# explorator_breakout_pcb_40mm.net
KiCad netlist of a schematic drawn in EAGLE
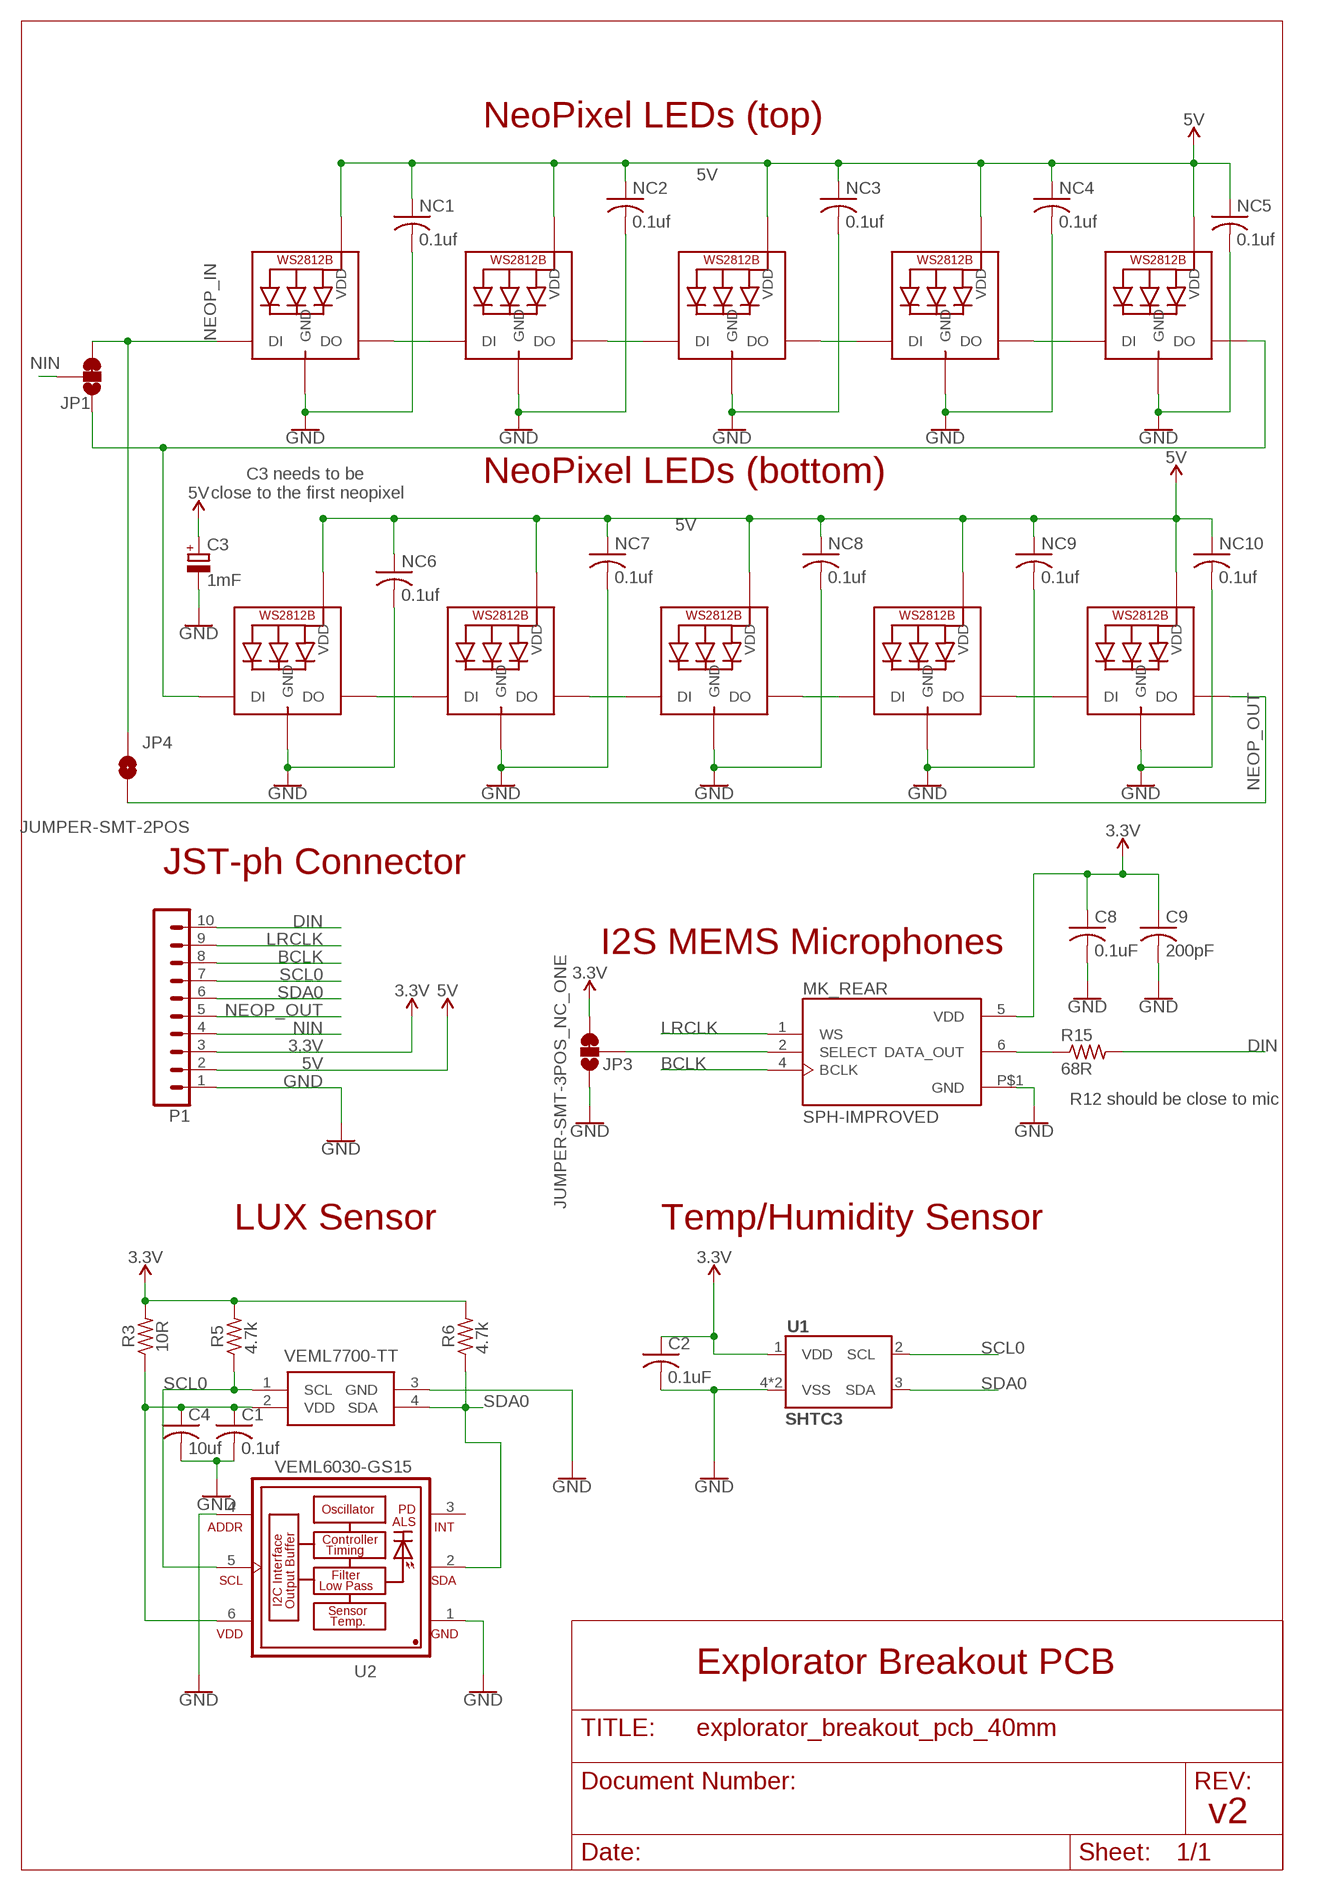
[diagram p0: schematic, sheet 1]

(export (version "E")
  (design (tool "Eeschema 10.0.6"))
  (components
    (comp (ref "C1")
      (value "0.1uf")
      (footprint "eagle-import:C0805")
      (libsource (lib "eagle-import") (part "C-USC0805"))
    )
    (comp (ref "C2")
      (value "0.1uF")
      (footprint "eagle-import:C0805")
      (libsource (lib "eagle-import") (part "C-USC0805"))
    )
    (comp (ref "C3")
      (value "1mF")
      (footprint "eagle-import:153CLV-1012")
      (libsource (lib "eagle-import") (part "CPOL-EU153CLV-1012"))
    )
    (comp (ref "C4")
      (value "10uf")
      (footprint "eagle-import:C0805")
      (libsource (lib "eagle-import") (part "C-USC0805"))
    )
    (comp (ref "C8")
      (value "0.1uF")
      (footprint "eagle-import:C0805")
      (libsource (lib "eagle-import") (part "C-USC0805"))
    )
    (comp (ref "C9")
      (value "200pF")
      (footprint "eagle-import:C0805")
      (libsource (lib "eagle-import") (part "C-USC0805"))
    )
    (comp (ref "JP1")
      (value "JUMPER-SMT-3POS_NC_ONE")
      (footprint "eagle-import:SMT-JUMPER_3_1-NC_TRACE_NO-SILK")
      (libsource (lib "eagle-import") (part "JUMPER-SMT-3POS_NC_ONE"))
    )
    (comp (ref "JP3")
      (value "JUMPER-SMT-3POS_NC_ONE")
      (footprint "eagle-import:SMT-JUMPER_3_1-NC_TRACE_NO-SILK")
      (libsource (lib "eagle-import") (part "JUMPER-SMT-3POS_NC_ONE"))
    )
    (comp (ref "JP4")
      (value "JUMPER-SMT-2POS")
      (footprint "eagle-import:SMT-JUMPER_2_NO_NO-SILK")
      (libsource (lib "eagle-import") (part "JUMPER-SMT-2POS"))
    )
    (comp (ref "MK_REAR")
      (value "SPH-IMPROVED")
      (footprint "eagle-import:MIC_SPH0645LM4H-B_LARGER_RING")
      (libsource (lib "eagle-import") (part "SPH-IMPROVED"))
    )
    (comp (ref "NC1")
      (value "0.1uf")
      (footprint "eagle-import:C0805")
      (libsource (lib "eagle-import") (part "C-USC0805"))
    )
    (comp (ref "NC2")
      (value "0.1uf")
      (footprint "eagle-import:C0805")
      (libsource (lib "eagle-import") (part "C-USC0805"))
    )
    (comp (ref "NC3")
      (value "0.1uf")
      (footprint "eagle-import:C0805")
      (libsource (lib "eagle-import") (part "C-USC0805"))
    )
    (comp (ref "NC4")
      (value "0.1uf")
      (footprint "eagle-import:C0805")
      (libsource (lib "eagle-import") (part "C-USC0805"))
    )
    (comp (ref "NC5")
      (value "0.1uf")
      (footprint "eagle-import:C0805")
      (libsource (lib "eagle-import") (part "C-USC0805"))
    )
    (comp (ref "NC6")
      (value "0.1uf")
      (footprint "eagle-import:C0805")
      (libsource (lib "eagle-import") (part "C-USC0805"))
    )
    (comp (ref "NC7")
      (value "0.1uf")
      (footprint "eagle-import:C0805")
      (libsource (lib "eagle-import") (part "C-USC0805"))
    )
    (comp (ref "NC8")
      (value "0.1uf")
      (footprint "eagle-import:C0805")
      (libsource (lib "eagle-import") (part "C-USC0805"))
    )
    (comp (ref "NC9")
      (value "0.1uf")
      (footprint "eagle-import:C0805")
      (libsource (lib "eagle-import") (part "C-USC0805"))
    )
    (comp (ref "NC10")
      (value "0.1uf")
      (footprint "eagle-import:C0805")
      (libsource (lib "eagle-import") (part "C-USC0805"))
    )
    (comp (ref "NEO_01")
      (value "WS2812")
      (footprint "eagle-import:WS2812B")
      (libsource (lib "eagle-import") (part "WS2812"))
    )
    (comp (ref "NEO_02")
      (value "WS2812")
      (footprint "eagle-import:WS2812B")
      (libsource (lib "eagle-import") (part "WS2812"))
    )
    (comp (ref "NEO_03")
      (value "WS2812")
      (footprint "eagle-import:WS2812B")
      (libsource (lib "eagle-import") (part "WS2812"))
    )
    (comp (ref "NEO_04")
      (value "WS2812")
      (footprint "eagle-import:WS2812B")
      (libsource (lib "eagle-import") (part "WS2812"))
    )
    (comp (ref "NEO_05")
      (value "WS2812")
      (footprint "eagle-import:WS2812B")
      (libsource (lib "eagle-import") (part "WS2812"))
    )
    (comp (ref "NEO_06")
      (value "WS2812")
      (footprint "eagle-import:WS2812B")
      (libsource (lib "eagle-import") (part "WS2812"))
    )
    (comp (ref "NEO_07")
      (value "WS2812")
      (footprint "eagle-import:WS2812B")
      (libsource (lib "eagle-import") (part "WS2812"))
    )
    (comp (ref "NEO_08")
      (value "WS2812")
      (footprint "eagle-import:WS2812B")
      (libsource (lib "eagle-import") (part "WS2812"))
    )
    (comp (ref "NEO_09")
      (value "WS2812")
      (footprint "eagle-import:WS2812B")
      (libsource (lib "eagle-import") (part "WS2812"))
    )
    (comp (ref "NEO_10")
      (value "WS2812")
      (footprint "eagle-import:WS2812B")
      (libsource (lib "eagle-import") (part "WS2812"))
    )
    (comp (ref "P1")
      (value "B10B-PH-K")
      (footprint "eagle-import:B10B-PH-K")
      (libsource (lib "eagle-import") (part "B10B-PH-K"))
    )
    (comp (ref "R3")
      (value "10R")
      (footprint "eagle-import:R0805")
      (libsource (lib "eagle-import") (part "R-US_R0805"))
    )
    (comp (ref "R5")
      (value "4.7k")
      (footprint "eagle-import:R0805")
      (libsource (lib "eagle-import") (part "R-US_R0805"))
    )
    (comp (ref "R6")
      (value "4.7k")
      (footprint "eagle-import:R0805")
      (libsource (lib "eagle-import") (part "R-US_R0805"))
    )
    (comp (ref "R15")
      (value "68R")
      (footprint "eagle-import:R0805")
      (libsource (lib "eagle-import") (part "R-US_R0805"))
    )
    (comp (ref "U1")
      (value "SHTC3")
      (footprint "eagle-import:SHTC3")
      (libsource (lib "eagle-import") (part "SHTC3"))
    )
    (comp (ref "U2")
      (value "VEML6030-GS15")
      (footprint "eagle-import:VISHAY_VEML6030_2X2X0.87")
      (fields (field (name "MF") "Vishay Semiconductor"))
      (libsource (lib "eagle-import") (part "VEML6030-GS15"))
    )
    (comp (ref "VEML_F")
      (value "VEML7700-TT")
      (footprint "eagle-import:VEML7700")
      (fields (field (name "MOUSER_PART_NUMBER") "78-VEML7700-TT") (field (name "RS_PART_NUMBER") "1226791P"))
      (libsource (lib "eagle-import") (part "VEML7700-TT"))
    )
  )
  (nets
    (net (code "1") (name "/BCLK") (class "Default")
      (node (ref "MK_REAR") (pin "4") (pinfunction "BCLK_4") (pintype "input"))
      (node (ref "P1") (pin "8") (pinfunction "8_8") (pintype "passive"))
    )
    (net (code "2") (name "/DIN") (class "Default")
      (node (ref "P1") (pin "10") (pinfunction "10_10") (pintype "passive"))
      (node (ref "R15") (pin "2") (pinfunction "2_2") (pintype "passive"))
    )
    (net (code "3") (name "/LRCLK") (class "Default")
      (node (ref "MK_REAR") (pin "1") (pinfunction "WS_1") (pintype "input"))
      (node (ref "P1") (pin "9") (pinfunction "9_9") (pintype "passive"))
    )
    (net (code "4") (name "/NEOP_IN") (class "Default")
      (node (ref "JP1") (pin "3") (pinfunction "3_3") (pintype "passive"))
      (node (ref "JP4") (pin "2") (pinfunction "2_2") (pintype "passive"))
      (node (ref "NEO_01") (pin "4-DIN") (pinfunction "DI_4-DIN") (pintype "input"))
    )
    (net (code "5") (name "/NEOP_OUT") (class "Default")
      (node (ref "JP4") (pin "1") (pinfunction "1_1") (pintype "passive"))
      (node (ref "NEO_10") (pin "2-DOUT") (pinfunction "DO_2-DOUT") (pintype "output"))
      (node (ref "P1") (pin "5") (pinfunction "5_5") (pintype "passive"))
    )
    (net (code "6") (name "/NIN") (class "Default")
      (node (ref "JP1") (pin "2") (pinfunction "2_2") (pintype "passive"))
      (node (ref "P1") (pin "4") (pinfunction "4_4") (pintype "passive"))
    )
    (net (code "7") (name "/SCL0") (class "Default")
      (node (ref "P1") (pin "7") (pinfunction "7_7") (pintype "passive"))
      (node (ref "R5") (pin "1") (pinfunction "1_1") (pintype "passive"))
      (node (ref "U1") (pin "2") (pinfunction "SCL_2") (pintype "bidirectional"))
      (node (ref "U2") (pin "5") (pinfunction "SCL_5") (pintype "input"))
      (node (ref "VEML_F") (pin "1") (pinfunction "SCL_1") (pintype "bidirectional"))
    )
    (net (code "8") (name "/SDA0") (class "Default")
      (node (ref "P1") (pin "6") (pinfunction "6_6") (pintype "passive"))
      (node (ref "R6") (pin "1") (pinfunction "1_1") (pintype "passive"))
      (node (ref "U1") (pin "3") (pinfunction "SDA_3") (pintype "bidirectional"))
      (node (ref "U2") (pin "2") (pinfunction "SDA_2") (pintype "bidirectional"))
      (node (ref "VEML_F") (pin "4") (pinfunction "SDA_4") (pintype "bidirectional"))
    )
    (net (code "9") (name "3.3V") (class "Default")
      (node (ref "C2") (pin "1") (pinfunction "1_1") (pintype "passive"))
      (node (ref "C8") (pin "1") (pinfunction "1_1") (pintype "passive"))
      (node (ref "C9") (pin "1") (pinfunction "1_1") (pintype "passive"))
      (node (ref "JP3") (pin "3") (pinfunction "3_3") (pintype "passive"))
      (node (ref "MK_REAR") (pin "5") (pinfunction "VDD_5") (pintype "power_in"))
      (node (ref "P1") (pin "3") (pinfunction "3_3") (pintype "passive"))
      (node (ref "R3") (pin "2") (pinfunction "2_2") (pintype "passive"))
      (node (ref "R5") (pin "2") (pinfunction "2_2") (pintype "passive"))
      (node (ref "R6") (pin "2") (pinfunction "2_2") (pintype "passive"))
      (node (ref "U1") (pin "1") (pinfunction "VDD_1") (pintype "bidirectional"))
    )
    (net (code "10") (name "5V") (class "Default")
      (node (ref "C3") (pin "+") (pinfunction "+_+") (pintype "passive"))
      (node (ref "NC1") (pin "1") (pinfunction "1_1") (pintype "passive"))
      (node (ref "NC10") (pin "1") (pinfunction "1_1") (pintype "passive"))
      (node (ref "NC2") (pin "1") (pinfunction "1_1") (pintype "passive"))
      (node (ref "NC3") (pin "1") (pinfunction "1_1") (pintype "passive"))
      (node (ref "NC4") (pin "1") (pinfunction "1_1") (pintype "passive"))
      (node (ref "NC5") (pin "1") (pinfunction "1_1") (pintype "passive"))
      (node (ref "NC6") (pin "1") (pinfunction "1_1") (pintype "passive"))
      (node (ref "NC7") (pin "1") (pinfunction "1_1") (pintype "passive"))
      (node (ref "NC8") (pin "1") (pinfunction "1_1") (pintype "passive"))
      (node (ref "NC9") (pin "1") (pinfunction "1_1") (pintype "passive"))
      (node (ref "NEO_01") (pin "1-VDD") (pinfunction "VDD_1-VDD") (pintype "power_in"))
      (node (ref "NEO_02") (pin "1-VDD") (pinfunction "VDD_1-VDD") (pintype "power_in"))
      (node (ref "NEO_03") (pin "1-VDD") (pinfunction "VDD_1-VDD") (pintype "power_in"))
      (node (ref "NEO_04") (pin "1-VDD") (pinfunction "VDD_1-VDD") (pintype "power_in"))
      (node (ref "NEO_05") (pin "1-VDD") (pinfunction "VDD_1-VDD") (pintype "power_in"))
      (node (ref "NEO_06") (pin "1-VDD") (pinfunction "VDD_1-VDD") (pintype "power_in"))
      (node (ref "NEO_07") (pin "1-VDD") (pinfunction "VDD_1-VDD") (pintype "power_in"))
      (node (ref "NEO_08") (pin "1-VDD") (pinfunction "VDD_1-VDD") (pintype "power_in"))
      (node (ref "NEO_09") (pin "1-VDD") (pinfunction "VDD_1-VDD") (pintype "power_in"))
      (node (ref "NEO_10") (pin "1-VDD") (pinfunction "VDD_1-VDD") (pintype "power_in"))
      (node (ref "P1") (pin "2") (pinfunction "2_2") (pintype "passive"))
    )
    (net (code "11") (name "GND") (class "Default")
      (node (ref "C1") (pin "2") (pinfunction "2_2") (pintype "passive"))
      (node (ref "C2") (pin "2") (pinfunction "2_2") (pintype "passive"))
      (node (ref "C3") (pin "-") (pinfunction "-_-") (pintype "passive"))
      (node (ref "C4") (pin "2") (pinfunction "2_2") (pintype "passive"))
      (node (ref "C8") (pin "2") (pinfunction "2_2") (pintype "passive"))
      (node (ref "C9") (pin "2") (pinfunction "2_2") (pintype "passive"))
      (node (ref "JP3") (pin "1") (pinfunction "1_1") (pintype "passive"))
      (node (ref "MK_REAR") (pin "P$1") (pinfunction "GND_P$1") (pintype "power_in"))
      (node (ref "NC1") (pin "2") (pinfunction "2_2") (pintype "passive"))
      (node (ref "NC10") (pin "2") (pinfunction "2_2") (pintype "passive"))
      (node (ref "NC2") (pin "2") (pinfunction "2_2") (pintype "passive"))
      (node (ref "NC3") (pin "2") (pinfunction "2_2") (pintype "passive"))
      (node (ref "NC4") (pin "2") (pinfunction "2_2") (pintype "passive"))
      (node (ref "NC5") (pin "2") (pinfunction "2_2") (pintype "passive"))
      (node (ref "NC6") (pin "2") (pinfunction "2_2") (pintype "passive"))
      (node (ref "NC7") (pin "2") (pinfunction "2_2") (pintype "passive"))
      (node (ref "NC8") (pin "2") (pinfunction "2_2") (pintype "passive"))
      (node (ref "NC9") (pin "2") (pinfunction "2_2") (pintype "passive"))
      (node (ref "NEO_01") (pin "3-GND") (pinfunction "GND_3-GND") (pintype "power_in"))
      (node (ref "NEO_02") (pin "3-GND") (pinfunction "GND_3-GND") (pintype "power_in"))
      (node (ref "NEO_03") (pin "3-GND") (pinfunction "GND_3-GND") (pintype "power_in"))
      (node (ref "NEO_04") (pin "3-GND") (pinfunction "GND_3-GND") (pintype "power_in"))
      (node (ref "NEO_05") (pin "3-GND") (pinfunction "GND_3-GND") (pintype "power_in"))
      (node (ref "NEO_06") (pin "3-GND") (pinfunction "GND_3-GND") (pintype "power_in"))
      (node (ref "NEO_07") (pin "3-GND") (pinfunction "GND_3-GND") (pintype "power_in"))
      (node (ref "NEO_08") (pin "3-GND") (pinfunction "GND_3-GND") (pintype "power_in"))
      (node (ref "NEO_09") (pin "3-GND") (pinfunction "GND_3-GND") (pintype "power_in"))
      (node (ref "NEO_10") (pin "3-GND") (pinfunction "GND_3-GND") (pintype "power_in"))
      (node (ref "P1") (pin "1") (pinfunction "1_1") (pintype "passive"))
      (node (ref "U1") (pin "4") (pinfunction "VSS_4") (pintype "bidirectional"))
      (node (ref "U1") (pin "5") (pinfunction "VSS_5") (pintype "bidirectional"))
      (node (ref "U2") (pin "1") (pinfunction "GND_1") (pintype "power_in"))
      (node (ref "U2") (pin "4") (pinfunction "ADDR_4") (pintype "bidirectional"))
      (node (ref "VEML_F") (pin "3") (pinfunction "GND_3") (pintype "bidirectional"))
    )
    (net (code "12") (name "Net-(MK_REAR-DATA_OUT)") (class "Default")
      (node (ref "MK_REAR") (pin "6") (pinfunction "DATA_OUT_6") (pintype "output"))
      (node (ref "R15") (pin "1") (pinfunction "1_1") (pintype "passive"))
    )
    (net (code "13") (name "Net-(MK_REAR-SELECT)") (class "Default")
      (node (ref "JP3") (pin "2") (pinfunction "2_2") (pintype "passive"))
      (node (ref "MK_REAR") (pin "2") (pinfunction "SELECT_2") (pintype "input"))
    )
    (net (code "14") (name "Net-(NEO_01-DO)") (class "Default")
      (node (ref "NEO_01") (pin "2-DOUT") (pinfunction "DO_2-DOUT") (pintype "output"))
      (node (ref "NEO_02") (pin "4-DIN") (pinfunction "DI_4-DIN") (pintype "input"))
    )
    (net (code "15") (name "Net-(NEO_02-DO)") (class "Default")
      (node (ref "NEO_02") (pin "2-DOUT") (pinfunction "DO_2-DOUT") (pintype "output"))
      (node (ref "NEO_03") (pin "4-DIN") (pinfunction "DI_4-DIN") (pintype "input"))
    )
    (net (code "16") (name "Net-(NEO_03-DO)") (class "Default")
      (node (ref "NEO_03") (pin "2-DOUT") (pinfunction "DO_2-DOUT") (pintype "output"))
      (node (ref "NEO_04") (pin "4-DIN") (pinfunction "DI_4-DIN") (pintype "input"))
    )
    (net (code "17") (name "Net-(NEO_04-DO)") (class "Default")
      (node (ref "NEO_04") (pin "2-DOUT") (pinfunction "DO_2-DOUT") (pintype "output"))
      (node (ref "NEO_05") (pin "4-DIN") (pinfunction "DI_4-DIN") (pintype "input"))
    )
    (net (code "18") (name "Net-(NEO_05-DO)") (class "Default")
      (node (ref "JP1") (pin "1") (pinfunction "1_1") (pintype "passive"))
      (node (ref "NEO_05") (pin "2-DOUT") (pinfunction "DO_2-DOUT") (pintype "output"))
      (node (ref "NEO_06") (pin "4-DIN") (pinfunction "DI_4-DIN") (pintype "input"))
    )
    (net (code "19") (name "Net-(NEO_06-DO)") (class "Default")
      (node (ref "NEO_06") (pin "2-DOUT") (pinfunction "DO_2-DOUT") (pintype "output"))
      (node (ref "NEO_07") (pin "4-DIN") (pinfunction "DI_4-DIN") (pintype "input"))
    )
    (net (code "20") (name "Net-(NEO_07-DO)") (class "Default")
      (node (ref "NEO_07") (pin "2-DOUT") (pinfunction "DO_2-DOUT") (pintype "output"))
      (node (ref "NEO_08") (pin "4-DIN") (pinfunction "DI_4-DIN") (pintype "input"))
    )
    (net (code "21") (name "Net-(NEO_08-DO)") (class "Default")
      (node (ref "NEO_08") (pin "2-DOUT") (pinfunction "DO_2-DOUT") (pintype "output"))
      (node (ref "NEO_09") (pin "4-DIN") (pinfunction "DI_4-DIN") (pintype "input"))
    )
    (net (code "22") (name "Net-(NEO_09-DO)") (class "Default")
      (node (ref "NEO_09") (pin "2-DOUT") (pinfunction "DO_2-DOUT") (pintype "output"))
      (node (ref "NEO_10") (pin "4-DIN") (pinfunction "DI_4-DIN") (pintype "input"))
    )
    (net (code "23") (name "Net-(U2-VDD)") (class "Default")
      (node (ref "C1") (pin "1") (pinfunction "1_1") (pintype "passive"))
      (node (ref "C4") (pin "1") (pinfunction "1_1") (pintype "passive"))
      (node (ref "R3") (pin "1") (pinfunction "1_1") (pintype "passive"))
      (node (ref "U2") (pin "6") (pinfunction "VDD_6") (pintype "power_in"))
      (node (ref "VEML_F") (pin "2") (pinfunction "VDD_2") (pintype "bidirectional"))
    )
    (net (code "24") (name "unconnected-(U2-INT-Pad3)") (class "Default")
      (node (ref "U2") (pin "3") (pinfunction "INT_3") (pintype "output"))
    )
  )
)
